# DC.net
KiCad netlist of a schematic drawn in Altium Designer
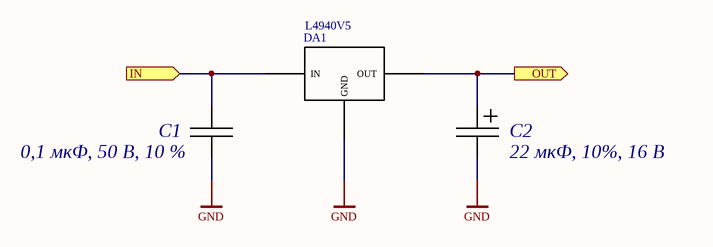
[diagram p0: DC.SchDoc]

(export (version "E")
  (design (tool "Eeschema 10.0.6"))
  (components
    (comp (ref "C1")
      (value "0,1 мкФ, 50 В, 10 %")
      (footprint "CAP: 0805")
      (description "Конденсатор")
      (fields
        (field (name "PARTNUMBER") "GRM21BR71H104K")
        (field (name "MANUFACTURER") "Murata Manufacturing")
      )
      (libsource (lib "AltiumDatabaseVM") (part "CAP_1"))
    )
    (comp (ref "C2")
      (value "22 мкФ, 10%, 16 В")
      (footprint "CAP: TANTAL-C")
      (description "Конденсатор")
      (fields (field (name "PARTNUMBER") "TECAP22/16VC10") (field (name "MANUFACTURER") "Китай"))
      (libsource (lib "AltiumDatabaseVM") (part "CAP"))
    )
    (comp (ref "DA1")
      (value "L4940V5")
      (footprint "TO220_L")
      (description "LDO регуляторы напряжения 5.0V 1.5A Positive")
      (fields (field (name "PARTNUMBER") "L4940V5_L") (field (name "MANUFACTURER") "STMicroelectronics"))
      (libsource (lib "AltiumDatabaseVM") (part "linear_stabilizer"))
    )
  )
  (nets
    (net (code "1") (name "/IN") (class "Default")
      (node (ref "C1") (pin "2") (pinfunction "2_2") (pintype "passive"))
      (node (ref "DA1") (pin "1") (pinfunction "IN_1") (pintype "passive"))
    )
    (net (code "2") (name "/OUT") (class "Default")
      (node (ref "C2") (pin "1") (pinfunction "1_1") (pintype "passive"))
      (node (ref "DA1") (pin "3") (pinfunction "OUT_3") (pintype "passive"))
    )
    (net (code "3") (name "GND") (class "Default")
      (node (ref "C1") (pin "1") (pinfunction "1_1") (pintype "passive"))
      (node (ref "C2") (pin "2") (pinfunction "2_2") (pintype "passive"))
      (node (ref "DA1") (pin "2") (pinfunction "GND_2") (pintype "passive"))
    )
  )
)
